# Digital_Output.net
KiCad netlist of a schematic drawn in EAGLE
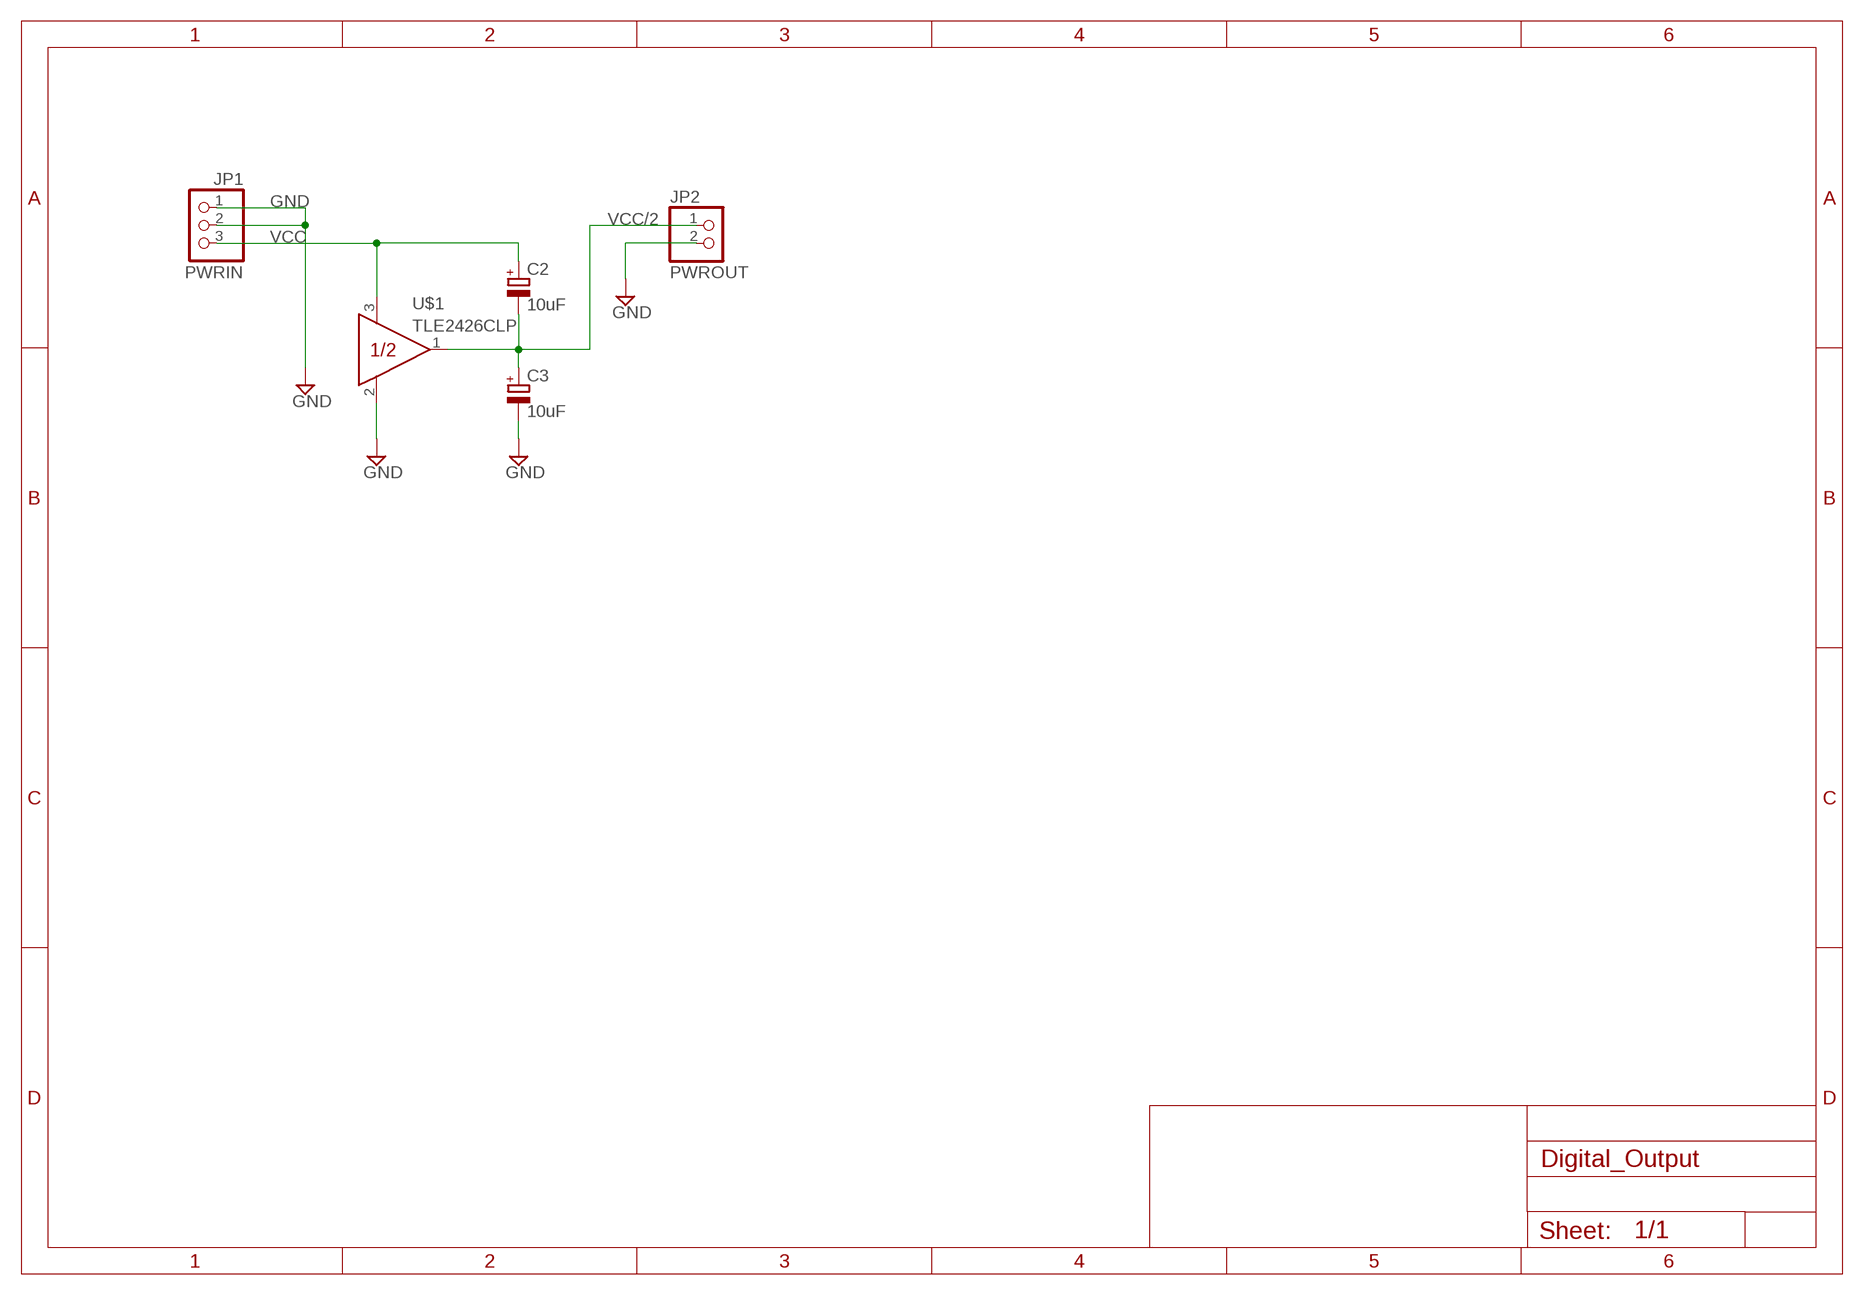
[diagram p0: schematic, sheet 1]

(export (version "E")
  (design (tool "Eeschema 10.0.6"))
  (components
    (comp (ref "C2")
      (value "10uF")
      (footprint "eagle-import:E2,5-5")
      (libsource (lib "eagle-import") (part "CPOL-EUE2.5-5"))
    )
    (comp (ref "C3")
      (value "10uF")
      (footprint "eagle-import:E2,5-5")
      (libsource (lib "eagle-import") (part "CPOL-EUE2.5-5"))
    )
    (comp (ref "JP1")
      (value "PWRIN")
      (footprint "eagle-import:1X03")
      (libsource (lib "eagle-import") (part "PINHD-1X3"))
    )
    (comp (ref "JP2")
      (value "PWROUT")
      (footprint "eagle-import:1X02")
      (libsource (lib "eagle-import") (part "PINHD-1X2"))
    )
    (comp (ref "U$1")
      (value "TLE2426CLP")
      (footprint "eagle-import:TO226AA")
      (libsource (lib "eagle-import") (part "TLE2426LPC"))
    )
  )
  (nets
    (net (code "1") (name "/VCC") (class "Default")
      (node (ref "C2") (pin "+") (pinfunction "+_+") (pintype "passive"))
      (node (ref "JP1") (pin "3") (pinfunction "3_3") (pintype "passive"))
      (node (ref "U$1") (pin "3") (pinfunction "IN_3") (pintype "passive"))
    )
    (net (code "2") (name "/VCC{slash}2") (class "Default")
      (node (ref "C2") (pin "-") (pinfunction "-_-") (pintype "passive"))
      (node (ref "C3") (pin "+") (pinfunction "+_+") (pintype "passive"))
      (node (ref "JP2") (pin "1") (pinfunction "1_1") (pintype "passive"))
      (node (ref "U$1") (pin "1") (pinfunction "OUT_1") (pintype "passive"))
    )
    (net (code "3") (name "GND") (class "Default")
      (node (ref "C3") (pin "-") (pinfunction "-_-") (pintype "passive"))
      (node (ref "JP1") (pin "1") (pinfunction "1_1") (pintype "passive"))
      (node (ref "JP1") (pin "2") (pinfunction "2_2") (pintype "passive"))
      (node (ref "JP2") (pin "2") (pinfunction "2_2") (pintype "passive"))
      (node (ref "U$1") (pin "2") (pinfunction "COM_2") (pintype "passive"))
    )
  )
)
